# 3DG_V2.net
KiCad netlist of a schematic drawn in EAGLE
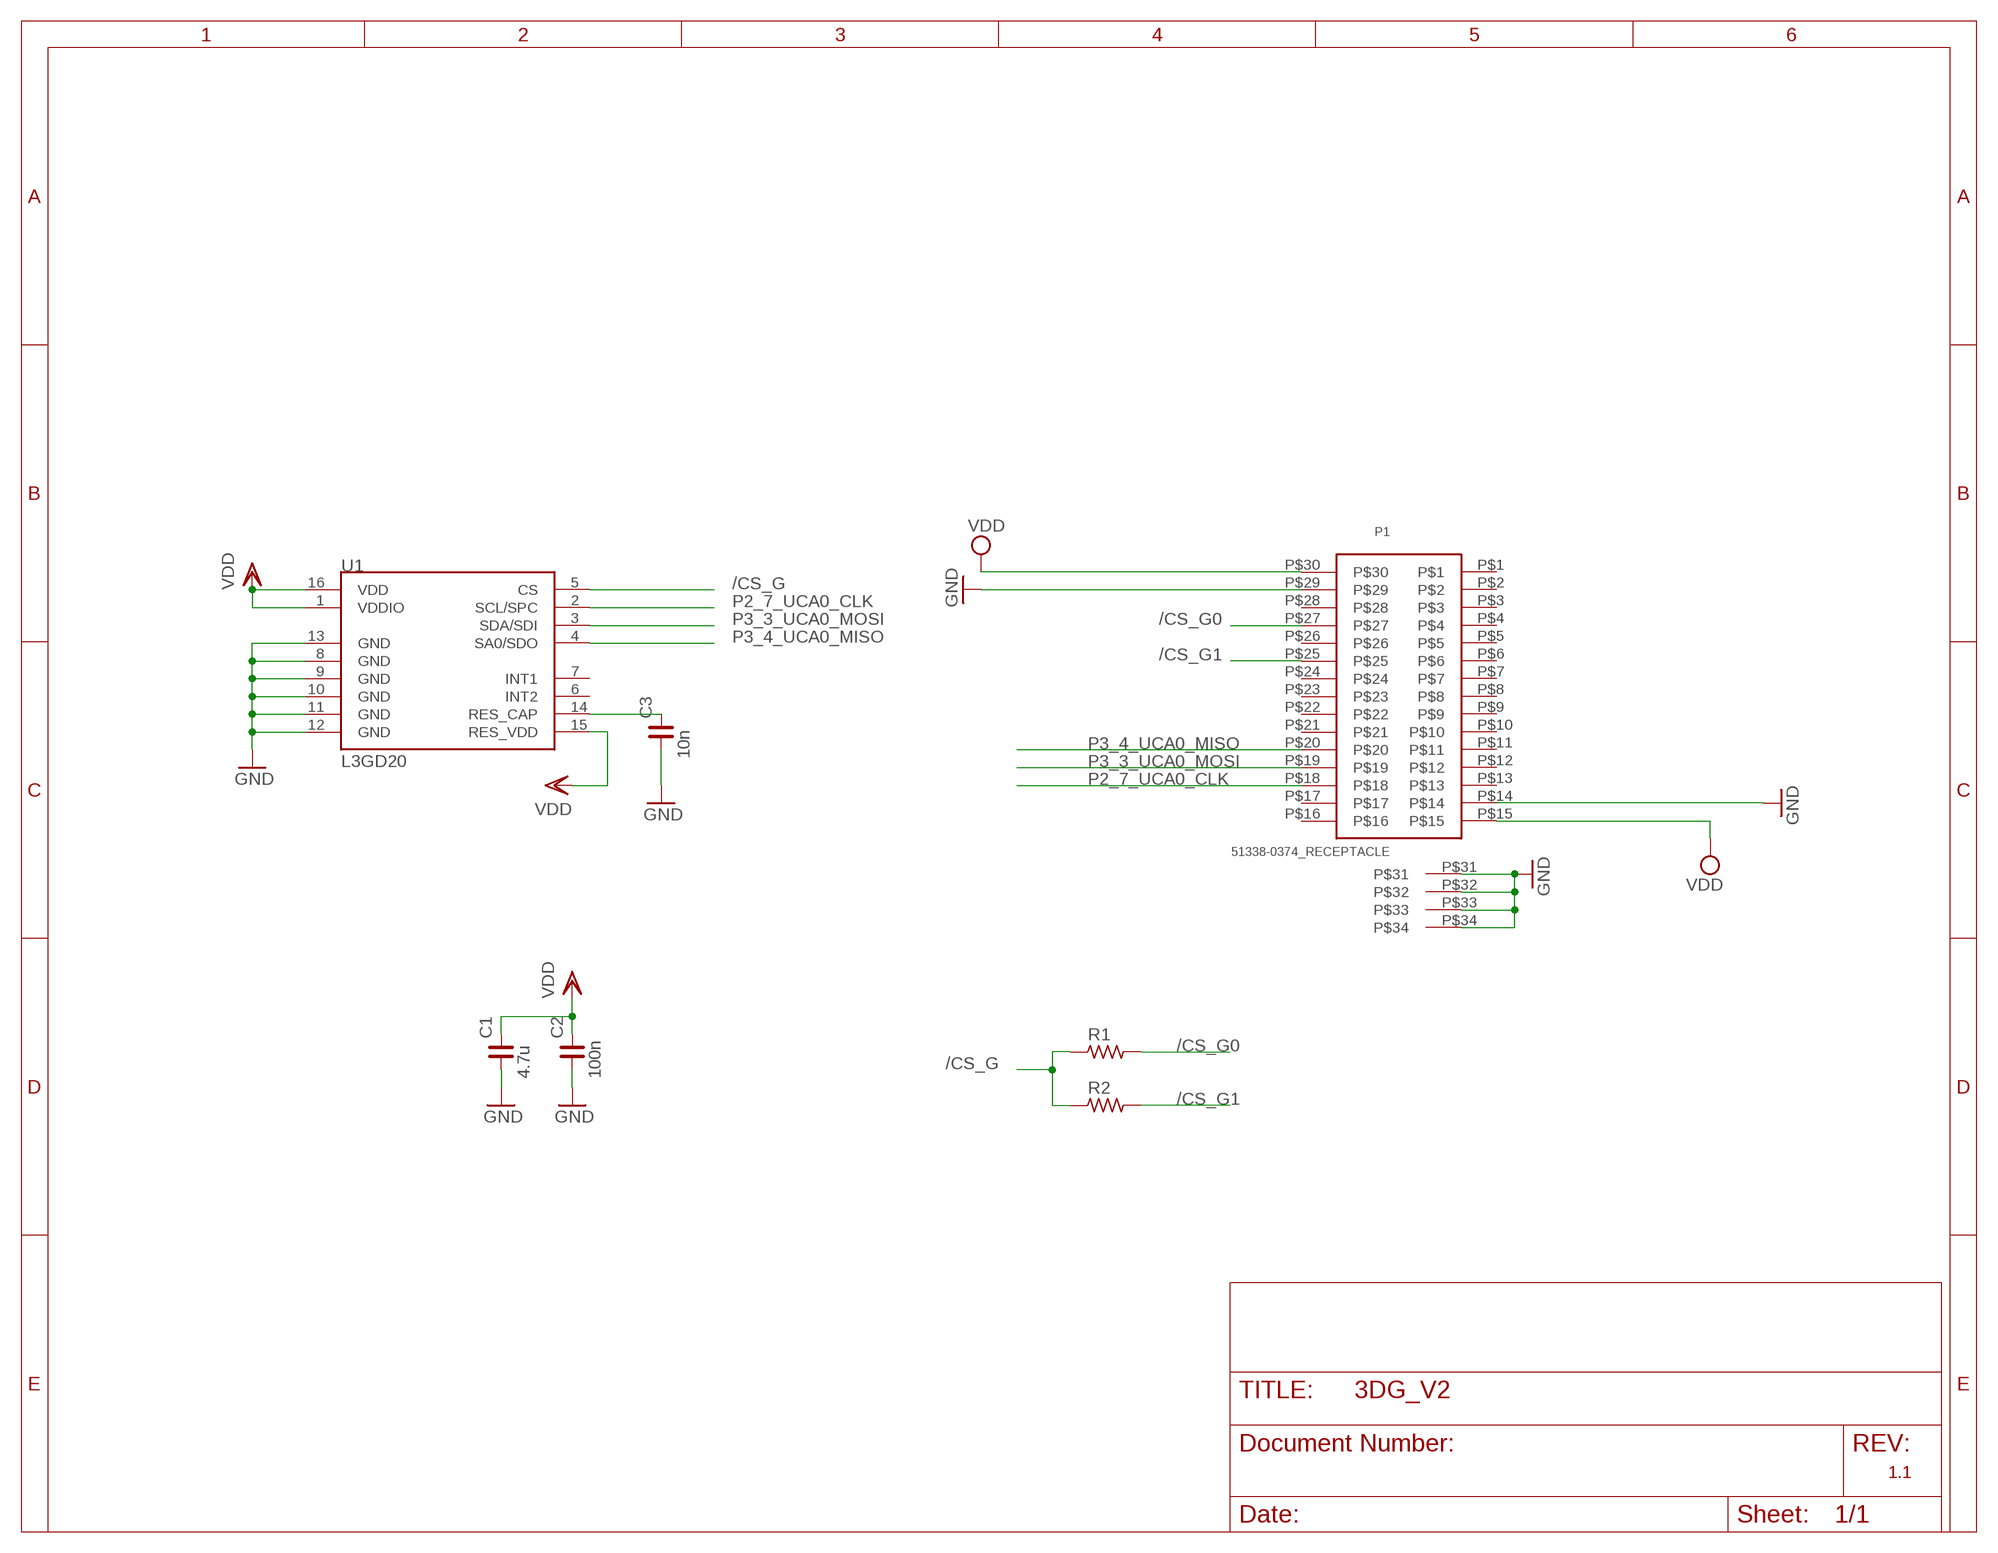
[diagram p0: schematic, sheet 1]

(export (version "E")
  (design (tool "Eeschema 10.0.6"))
  (components
    (comp (ref "C1")
      (value "4.7u")
      (footprint "eagle-import:C0402")
      (libsource (lib "eagle-import") (part "C_0402"))
    )
    (comp (ref "C2")
      (value "100n")
      (footprint "eagle-import:C0402")
      (libsource (lib "eagle-import") (part "C_0402"))
    )
    (comp (ref "C3")
      (value "10n")
      (footprint "eagle-import:C0402")
      (libsource (lib "eagle-import") (part "C_0402"))
    )
    (comp (ref "P1")
      (value "51338-0374_RECEPTACLE")
      (footprint "eagle-import:51338-0374_RECEPTACLE")
      (libsource (lib "eagle-import") (part "51338-0374_RECEPTACLE"))
    )
    (comp (ref "R1")
      (value "R_0402")
      (footprint "eagle-import:R0402")
      (libsource (lib "eagle-import") (part "R_0402"))
    )
    (comp (ref "R2")
      (value "R_0402")
      (footprint "eagle-import:R0402")
      (libsource (lib "eagle-import") (part "R_0402"))
    )
    (comp (ref "U1")
      (value "L3GD20")
      (footprint "eagle-import:LGA16-4X4")
      (libsource (lib "eagle-import") (part "L3GD20"))
    )
  )
  (nets
    (net (code "1") (name "/P2_7_UCA0_CLK") (class "Default")
      (node (ref "P1") (pin "P$18") (pinfunction "P$18_P$18") (pintype "bidirectional"))
      (node (ref "U1") (pin "2") (pinfunction "SCL/SPC_2") (pintype "bidirectional"))
    )
    (net (code "2") (name "/P3_3_UCA0_MOSI") (class "Default")
      (node (ref "P1") (pin "P$19") (pinfunction "P$19_P$19") (pintype "bidirectional"))
      (node (ref "U1") (pin "3") (pinfunction "SDA/SDI_3") (pintype "bidirectional"))
    )
    (net (code "3") (name "/P3_4_UCA0_MISO") (class "Default")
      (node (ref "P1") (pin "P$20") (pinfunction "P$20_P$20") (pintype "bidirectional"))
      (node (ref "U1") (pin "4") (pinfunction "SA0/SDO_4") (pintype "bidirectional"))
    )
    (net (code "4") (name "/{slash}CS_G") (class "Default")
      (node (ref "R1") (pin "1") (pinfunction "1_1") (pintype "passive"))
      (node (ref "R2") (pin "1") (pinfunction "1_1") (pintype "passive"))
      (node (ref "U1") (pin "5") (pinfunction "CS_5") (pintype "bidirectional"))
    )
    (net (code "5") (name "/{slash}CS_G0") (class "Default")
      (node (ref "P1") (pin "P$27") (pinfunction "P$27_P$27") (pintype "bidirectional"))
      (node (ref "R1") (pin "2") (pinfunction "2_2") (pintype "passive"))
    )
    (net (code "6") (name "/{slash}CS_G1") (class "Default")
      (node (ref "P1") (pin "P$25") (pinfunction "P$25_P$25") (pintype "bidirectional"))
      (node (ref "R2") (pin "2") (pinfunction "2_2") (pintype "passive"))
    )
    (net (code "7") (name "GND") (class "Default")
      (node (ref "C1") (pin "1") (pinfunction "1_1") (pintype "passive"))
      (node (ref "C2") (pin "1") (pinfunction "1_1") (pintype "passive"))
      (node (ref "C3") (pin "1") (pinfunction "1_1") (pintype "passive"))
      (node (ref "P1") (pin "P$14") (pinfunction "P$14_P$14") (pintype "bidirectional"))
      (node (ref "P1") (pin "P$29") (pinfunction "P$29_P$29") (pintype "bidirectional"))
      (node (ref "P1") (pin "P$31") (pinfunction "P$31_P$31") (pintype "bidirectional"))
      (node (ref "P1") (pin "P$32") (pinfunction "P$32_P$32") (pintype "bidirectional"))
      (node (ref "P1") (pin "P$33") (pinfunction "P$33_P$33") (pintype "bidirectional"))
      (node (ref "P1") (pin "P$34") (pinfunction "P$34_P$34") (pintype "bidirectional"))
      (node (ref "U1") (pin "10") (pinfunction "GND_10") (pintype "bidirectional"))
      (node (ref "U1") (pin "11") (pinfunction "GND_11") (pintype "bidirectional"))
      (node (ref "U1") (pin "12") (pinfunction "GND_12") (pintype "bidirectional"))
      (node (ref "U1") (pin "13") (pinfunction "GND_13") (pintype "bidirectional"))
      (node (ref "U1") (pin "8") (pinfunction "GND_8") (pintype "bidirectional"))
      (node (ref "U1") (pin "9") (pinfunction "GND_9") (pintype "bidirectional"))
    )
    (net (code "8") (name "Net-(U1-RES_CAP)") (class "Default")
      (node (ref "C3") (pin "2") (pinfunction "2_2") (pintype "passive"))
      (node (ref "U1") (pin "14") (pinfunction "RES_CAP_14") (pintype "bidirectional"))
    )
    (net (code "9") (name "VDD") (class "Default")
      (node (ref "C1") (pin "2") (pinfunction "2_2") (pintype "passive"))
      (node (ref "C2") (pin "2") (pinfunction "2_2") (pintype "passive"))
      (node (ref "P1") (pin "P$15") (pinfunction "P$15_P$15") (pintype "bidirectional"))
      (node (ref "P1") (pin "P$30") (pinfunction "P$30_P$30") (pintype "bidirectional"))
      (node (ref "U1") (pin "1") (pinfunction "VDDIO_1") (pintype "bidirectional"))
      (node (ref "U1") (pin "15") (pinfunction "RES_VDD_15") (pintype "bidirectional"))
      (node (ref "U1") (pin "16") (pinfunction "VDD_16") (pintype "bidirectional"))
    )
    (net (code "10") (name "unconnected-(P1-PadP$1)") (class "Default")
      (node (ref "P1") (pin "P$1") (pinfunction "P$1_P$1") (pintype "bidirectional"))
    )
    (net (code "11") (name "unconnected-(P1-PadP$2)") (class "Default")
      (node (ref "P1") (pin "P$2") (pinfunction "P$2_P$2") (pintype "bidirectional"))
    )
    (net (code "12") (name "unconnected-(P1-PadP$3)") (class "Default")
      (node (ref "P1") (pin "P$3") (pinfunction "P$3_P$3") (pintype "bidirectional"))
    )
    (net (code "13") (name "unconnected-(P1-PadP$4)") (class "Default")
      (node (ref "P1") (pin "P$4") (pinfunction "P$4_P$4") (pintype "bidirectional"))
    )
    (net (code "14") (name "unconnected-(P1-PadP$5)") (class "Default")
      (node (ref "P1") (pin "P$5") (pinfunction "P$5_P$5") (pintype "bidirectional"))
    )
    (net (code "15") (name "unconnected-(P1-PadP$6)") (class "Default")
      (node (ref "P1") (pin "P$6") (pinfunction "P$6_P$6") (pintype "bidirectional"))
    )
    (net (code "16") (name "unconnected-(P1-PadP$7)") (class "Default")
      (node (ref "P1") (pin "P$7") (pinfunction "P$7_P$7") (pintype "bidirectional"))
    )
    (net (code "17") (name "unconnected-(P1-PadP$8)") (class "Default")
      (node (ref "P1") (pin "P$8") (pinfunction "P$8_P$8") (pintype "bidirectional"))
    )
    (net (code "18") (name "unconnected-(P1-PadP$9)") (class "Default")
      (node (ref "P1") (pin "P$9") (pinfunction "P$9_P$9") (pintype "bidirectional"))
    )
    (net (code "19") (name "unconnected-(P1-PadP$10)") (class "Default")
      (node (ref "P1") (pin "P$10") (pinfunction "P$10_P$10") (pintype "bidirectional"))
    )
    (net (code "20") (name "unconnected-(P1-PadP$11)") (class "Default")
      (node (ref "P1") (pin "P$11") (pinfunction "P$11_P$11") (pintype "bidirectional"))
    )
    (net (code "21") (name "unconnected-(P1-PadP$12)") (class "Default")
      (node (ref "P1") (pin "P$12") (pinfunction "P$12_P$12") (pintype "bidirectional"))
    )
    (net (code "22") (name "unconnected-(P1-PadP$13)") (class "Default")
      (node (ref "P1") (pin "P$13") (pinfunction "P$13_P$13") (pintype "bidirectional"))
    )
    (net (code "23") (name "unconnected-(P1-PadP$16)") (class "Default")
      (node (ref "P1") (pin "P$16") (pinfunction "P$16_P$16") (pintype "bidirectional"))
    )
    (net (code "24") (name "unconnected-(P1-PadP$17)") (class "Default")
      (node (ref "P1") (pin "P$17") (pinfunction "P$17_P$17") (pintype "bidirectional"))
    )
    (net (code "25") (name "unconnected-(P1-PadP$21)") (class "Default")
      (node (ref "P1") (pin "P$21") (pinfunction "P$21_P$21") (pintype "bidirectional"))
    )
    (net (code "26") (name "unconnected-(P1-PadP$22)") (class "Default")
      (node (ref "P1") (pin "P$22") (pinfunction "P$22_P$22") (pintype "bidirectional"))
    )
    (net (code "27") (name "unconnected-(P1-PadP$23)") (class "Default")
      (node (ref "P1") (pin "P$23") (pinfunction "P$23_P$23") (pintype "bidirectional"))
    )
    (net (code "28") (name "unconnected-(P1-PadP$24)") (class "Default")
      (node (ref "P1") (pin "P$24") (pinfunction "P$24_P$24") (pintype "bidirectional"))
    )
    (net (code "29") (name "unconnected-(P1-PadP$26)") (class "Default")
      (node (ref "P1") (pin "P$26") (pinfunction "P$26_P$26") (pintype "bidirectional"))
    )
    (net (code "30") (name "unconnected-(P1-PadP$28)") (class "Default")
      (node (ref "P1") (pin "P$28") (pinfunction "P$28_P$28") (pintype "bidirectional"))
    )
    (net (code "31") (name "unconnected-(U1-INT1-Pad7)") (class "Default")
      (node (ref "U1") (pin "7") (pinfunction "INT1_7") (pintype "bidirectional"))
    )
    (net (code "32") (name "unconnected-(U1-INT2-Pad6)") (class "Default")
      (node (ref "U1") (pin "6") (pinfunction "INT2_6") (pintype "bidirectional"))
    )
  )
)
